# Smart_home_system.net
KiCad netlist of a schematic drawn in EasyEDA
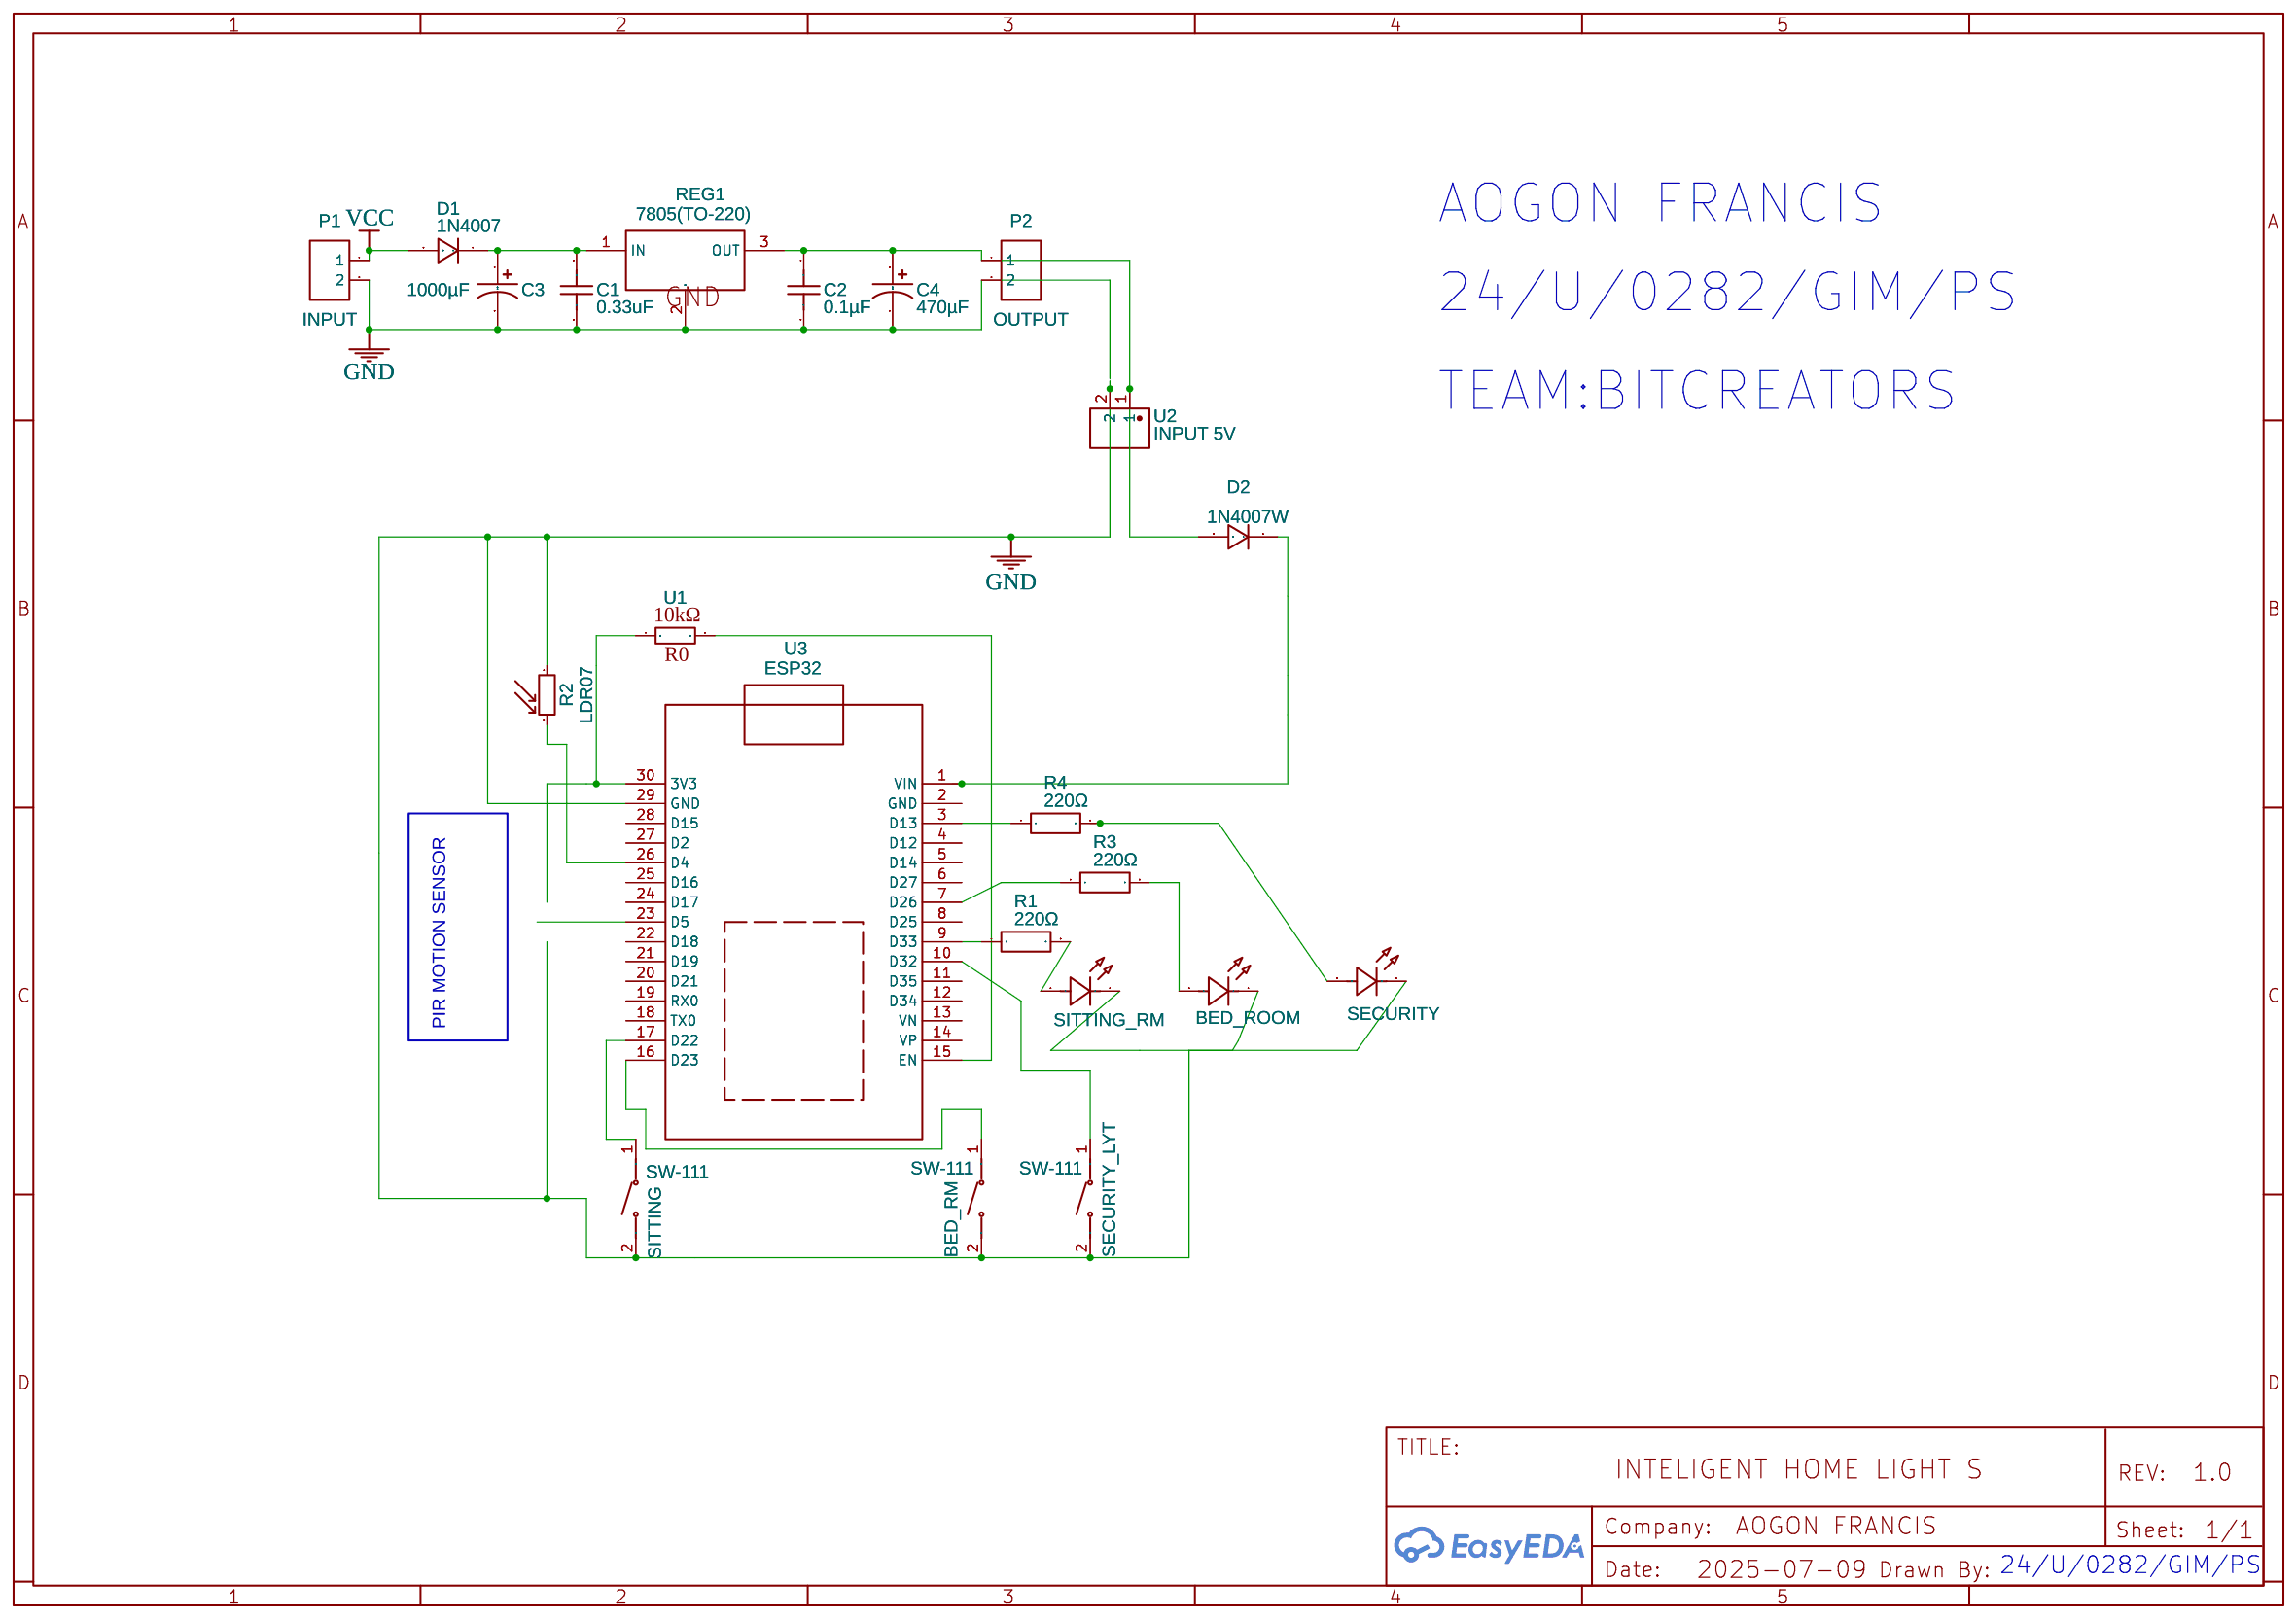
[diagram p0: schematic sheet]

(export (version "E")
  (design (tool "Eeschema 10.0.6"))
  (components
    (comp (ref "BED_RM")
      (value "SW-111")
      (fields (field (name "Manufacturer") "Shinmei(日本神明)"))
      (libsource (lib "") (part "SW-111_2"))
    )
    (comp (ref "C1") (value "0.33uF") (libsource (lib "") (part "C_RAD-0.1_US")))
    (comp (ref "C2") (value "0.1µF") (libsource (lib "") (part "C_RAD-0.1_US")))
    (comp (ref "C3") (value "1000µF") (libsource (lib "") (part "CE_TH_D3.0×F1.5_US_1")))
    (comp (ref "C4") (value "470µF") (libsource (lib "") (part "CE_TH_D3.0×F1.5_US")))
    (comp (ref "D1")
      (value "1N4007")
      (fields (field (name "Manufacturer") "SEMTECH"))
      (libsource (lib "") (part "1N4007"))
    )
    (comp (ref "D2")
      (value "1N4007W")
      (fields (field (name "Manufacturer") "BLUE ROCKET"))
      (libsource (lib "") (part "1N4007W"))
    )
    (comp (ref "LED1")
      (value "SECURITY")
      (fields
        (field (name "Manufacturer Part") "LTST-C190KRKT-TH")
        (field (name "Manufacturer") "LITEON(光宝)")
      )
      (libsource (lib "") (part "LTST-C190KRKT-TH"))
    )
    (comp (ref "LED2")
      (value "BED_ROOM")
      (fields
        (field (name "Manufacturer Part") "LTST-C190KRKT-TH")
        (field (name "Manufacturer") "LITEON(光宝)")
      )
      (libsource (lib "") (part "LTST-C190KRKT-TH"))
    )
    (comp (ref "P1") (value "INPUT") (libsource (lib "") (part "CONN-TH_2P-P5.00")))
    (comp (ref "P2") (value "OUTPUT") (libsource (lib "") (part "CONN-TH_2P-P5.00_1")))
    (comp (ref "R1") (value "220Ω") (libsource (lib "") (part "RESISTOR")))
    (comp (ref "R2") (value "LDR07") (libsource (lib "") (part "LDR07")))
    (comp (ref "R3") (value "220Ω") (libsource (lib "") (part "RESISTOR")))
    (comp (ref "R4") (value "220Ω") (libsource (lib "") (part "RESISTOR")))
    (comp (ref "REG1")
      (value "7805(TO-220)")
      (fields
        (field (name "Manufacturer Part") "L7805CV-DG")
        (field (name "Manufacturer") "STMicroelectronics")
      )
      (libsource (lib "") (part "7805(TO-220)"))
    )
    (comp (ref "SECURITY_LYT")
      (value "SW-111")
      (fields (field (name "Manufacturer") "Shinmei(日本神明)"))
      (libsource (lib "") (part "SW-111_1"))
    )
    (comp (ref "SITTING")
      (value "SW-111")
      (fields (field (name "Manufacturer") "Shinmei(日本神明)"))
      (libsource (lib "") (part "SW-111"))
    )
    (comp (ref "SITTING_RM")
      (value "LTST-C190KRKT-TH")
      (fields (field (name "Manufacturer") "LITEON(光宝)"))
      (libsource (lib "") (part "LTST-C190KRKT-TH_1"))
    )
    (comp (ref "U1")
      (value "10KΩ")
      (fields (field (name "Manufacturer Part") "Resistor 10kΩ"))
      (libsource (lib "") (part "Resistor 10KΩ"))
    )
    (comp (ref "U2")
      (value "INPUT 5V")
      (fields (field (name "Manufacturer Part") "197054001") (field (name "Manufacturer") "MOLEX"))
      (libsource (lib "") (part "197054001"))
    )
    (comp (ref "U3") (value "ESP32") (libsource (lib "") (part "MyESP32TypeC")))
  )
  (nets
    (net (code "1") (name "GND") (class "Default")
      (node (ref "BED_RM") (pin "2") (pinfunction "2_2") (pintype "unspecified"))
      (node (ref "C1") (pin "2") (pinfunction "2_2") (pintype "unspecified"))
      (node (ref "C2") (pin "2") (pinfunction "2_2") (pintype "unspecified"))
      (node (ref "C3") (pin "2") (pinfunction "2_2") (pintype "unspecified"))
      (node (ref "C4") (pin "2") (pinfunction "2_2") (pintype "unspecified"))
      (node (ref "LED2") (pin "1") (pinfunction "K_1") (pintype "unspecified"))
      (node (ref "P1") (pin "2") (pinfunction "2_2") (pintype "unspecified"))
      (node (ref "P2") (pin "2") (pinfunction "2_2") (pintype "unspecified"))
      (node (ref "R2") (pin "1") (pintype "unspecified"))
      (node (ref "REG1") (pin "2") (pinfunction "GND_2") (pintype "passive"))
      (node (ref "SECURITY_LYT") (pin "2") (pinfunction "2_2") (pintype "unspecified"))
      (node (ref "SITTING") (pin "2") (pinfunction "2_2") (pintype "unspecified"))
      (node (ref "U2") (pin "2") (pinfunction "2_2") (pintype "unspecified"))
      (node (ref "U3") (pin "29") (pinfunction "GND_29") (pintype "unspecified"))
    )
    (net (code "2") (name "Net-(D2-Pad2)") (class "Default")
      (node (ref "D2") (pin "2") (pinfunction "2_2") (pintype "unspecified"))
      (node (ref "U2") (pin "1") (pinfunction "1_1") (pintype "unspecified"))
    )
    (net (code "3") (name "Net-(LED1-A)") (class "Default")
      (node (ref "LED1") (pin "2") (pinfunction "A_2") (pintype "unspecified"))
      (node (ref "R4") (pin "2") (pinfunction "2_2") (pintype "unspecified"))
    )
    (net (code "4") (name "Net-(LED1-K)") (class "Default")
      (node (ref "LED1") (pin "1") (pinfunction "K_1") (pintype "unspecified"))
      (node (ref "SITTING_RM") (pin "1") (pinfunction "K_1") (pintype "unspecified"))
    )
    (net (code "5") (name "Net-(LED2-A)") (class "Default")
      (node (ref "LED2") (pin "2") (pinfunction "A_2") (pintype "unspecified"))
      (node (ref "R3") (pin "2") (pinfunction "2_2") (pintype "unspecified"))
    )
    (net (code "6") (name "Net-(REG1-IN)") (class "Default")
      (node (ref "C1") (pin "1") (pinfunction "1_1") (pintype "unspecified"))
      (node (ref "C3") (pin "1") (pinfunction "1_1") (pintype "unspecified"))
      (node (ref "D1") (pin "1") (pinfunction "1_1") (pintype "unspecified"))
      (node (ref "REG1") (pin "1") (pinfunction "IN_1") (pintype "passive"))
    )
    (net (code "7") (name "Net-(REG1-OUT)") (class "Default")
      (node (ref "C2") (pin "1") (pinfunction "1_1") (pintype "unspecified"))
      (node (ref "C4") (pin "1") (pinfunction "1_1") (pintype "unspecified"))
      (node (ref "P2") (pin "1") (pinfunction "1_1") (pintype "unspecified"))
      (node (ref "REG1") (pin "3") (pinfunction "OUT_3") (pintype "passive"))
    )
    (net (code "8") (name "Net-(SITTING_RM-A)") (class "Default")
      (node (ref "R1") (pin "2") (pinfunction "2_2") (pintype "unspecified"))
      (node (ref "SITTING_RM") (pin "2") (pinfunction "A_2") (pintype "unspecified"))
    )
    (net (code "9") (name "Net-(U3-3V3)") (class "Default")
      (node (ref "U1") (pin "1") (pinfunction "0_1") (pintype "input"))
      (node (ref "U3") (pin "30") (pinfunction "3V3_30") (pintype "unspecified"))
    )
    (net (code "10") (name "Net-(U3-D4)") (class "Default")
      (node (ref "R2") (pin "2") (pintype "unspecified"))
      (node (ref "U3") (pin "26") (pinfunction "D4_26") (pintype "unspecified"))
    )
    (net (code "11") (name "Net-(U3-D13)") (class "Default")
      (node (ref "R4") (pin "1") (pinfunction "1_1") (pintype "unspecified"))
      (node (ref "U3") (pin "3") (pinfunction "D13_3") (pintype "unspecified"))
    )
    (net (code "12") (name "Net-(U3-D22)") (class "Default")
      (node (ref "SITTING") (pin "1") (pinfunction "1_1") (pintype "unspecified"))
      (node (ref "U3") (pin "17") (pinfunction "D22_17") (pintype "unspecified"))
    )
    (net (code "13") (name "Net-(U3-D23)") (class "Default")
      (node (ref "BED_RM") (pin "1") (pinfunction "1_1") (pintype "unspecified"))
      (node (ref "U3") (pin "16") (pinfunction "D23_16") (pintype "unspecified"))
    )
    (net (code "14") (name "Net-(U3-D26)") (class "Default")
      (node (ref "R3") (pin "1") (pinfunction "1_1") (pintype "unspecified"))
      (node (ref "U3") (pin "7") (pinfunction "D26_7") (pintype "unspecified"))
    )
    (net (code "15") (name "Net-(U3-D32)") (class "Default")
      (node (ref "SECURITY_LYT") (pin "1") (pinfunction "1_1") (pintype "unspecified"))
      (node (ref "U3") (pin "10") (pinfunction "D32_10") (pintype "unspecified"))
    )
    (net (code "16") (name "Net-(U3-D33)") (class "Default")
      (node (ref "R1") (pin "1") (pinfunction "1_1") (pintype "unspecified"))
      (node (ref "U3") (pin "9") (pinfunction "D33_9") (pintype "unspecified"))
    )
    (net (code "17") (name "Net-(U3-EN)") (class "Default")
      (node (ref "U1") (pin "2") (pinfunction "0_2") (pintype "input"))
      (node (ref "U3") (pin "15") (pinfunction "EN_15") (pintype "unspecified"))
    )
    (net (code "18") (name "Net-(U3-VIN)") (class "Default")
      (node (ref "D2") (pin "1") (pinfunction "1_1") (pintype "unspecified"))
      (node (ref "U3") (pin "1") (pinfunction "VIN_1") (pintype "unspecified"))
    )
    (net (code "19") (name "VCC") (class "Default")
      (node (ref "D1") (pin "2") (pinfunction "2_2") (pintype "unspecified"))
      (node (ref "P1") (pin "1") (pinfunction "1_1") (pintype "unspecified"))
    )
    (net (code "20") (name "unconnected-(U3-D2-Pad27)") (class "Default")
      (node (ref "U3") (pin "27") (pinfunction "D2_27") (pintype "unspecified"))
    )
    (net (code "21") (name "unconnected-(U3-D5-Pad23)") (class "Default")
      (node (ref "U3") (pin "23") (pinfunction "D5_23") (pintype "unspecified"))
    )
    (net (code "22") (name "unconnected-(U3-D12-Pad4)") (class "Default")
      (node (ref "U3") (pin "4") (pinfunction "D12_4") (pintype "unspecified"))
    )
    (net (code "23") (name "unconnected-(U3-D14-Pad5)") (class "Default")
      (node (ref "U3") (pin "5") (pinfunction "D14_5") (pintype "unspecified"))
    )
    (net (code "24") (name "unconnected-(U3-D15-Pad28)") (class "Default")
      (node (ref "U3") (pin "28") (pinfunction "D15_28") (pintype "unspecified"))
    )
    (net (code "25") (name "unconnected-(U3-D16-Pad25)") (class "Default")
      (node (ref "U3") (pin "25") (pinfunction "D16_25") (pintype "unspecified"))
    )
    (net (code "26") (name "unconnected-(U3-D17-Pad24)") (class "Default")
      (node (ref "U3") (pin "24") (pinfunction "D17_24") (pintype "unspecified"))
    )
    (net (code "27") (name "unconnected-(U3-D18-Pad22)") (class "Default")
      (node (ref "U3") (pin "22") (pinfunction "D18_22") (pintype "unspecified"))
    )
    (net (code "28") (name "unconnected-(U3-D19-Pad21)") (class "Default")
      (node (ref "U3") (pin "21") (pinfunction "D19_21") (pintype "unspecified"))
    )
    (net (code "29") (name "unconnected-(U3-D21-Pad20)") (class "Default")
      (node (ref "U3") (pin "20") (pinfunction "D21_20") (pintype "unspecified"))
    )
    (net (code "30") (name "unconnected-(U3-D25-Pad8)") (class "Default")
      (node (ref "U3") (pin "8") (pinfunction "D25_8") (pintype "unspecified"))
    )
    (net (code "31") (name "unconnected-(U3-D27-Pad6)") (class "Default")
      (node (ref "U3") (pin "6") (pinfunction "D27_6") (pintype "unspecified"))
    )
    (net (code "32") (name "unconnected-(U3-D34-Pad12)") (class "Default")
      (node (ref "U3") (pin "12") (pinfunction "D34_12") (pintype "unspecified"))
    )
    (net (code "33") (name "unconnected-(U3-D35-Pad11)") (class "Default")
      (node (ref "U3") (pin "11") (pinfunction "D35_11") (pintype "unspecified"))
    )
    (net (code "34") (name "unconnected-(U3-GND-Pad2)") (class "Default")
      (node (ref "U3") (pin "2") (pinfunction "GND_2") (pintype "unspecified"))
    )
    (net (code "35") (name "unconnected-(U3-RX0-Pad19)") (class "Default")
      (node (ref "U3") (pin "19") (pinfunction "RX0_19") (pintype "unspecified"))
    )
    (net (code "36") (name "unconnected-(U3-TX0-Pad18)") (class "Default")
      (node (ref "U3") (pin "18") (pinfunction "TX0_18") (pintype "unspecified"))
    )
    (net (code "37") (name "unconnected-(U3-VN-Pad13)") (class "Default")
      (node (ref "U3") (pin "13") (pinfunction "VN_13") (pintype "unspecified"))
    )
    (net (code "38") (name "unconnected-(U3-VP-Pad14)") (class "Default")
      (node (ref "U3") (pin "14") (pinfunction "VP_14") (pintype "unspecified"))
    )
  )
)
